# experiment.net
KiCad netlist of a schematic drawn in EAGLE
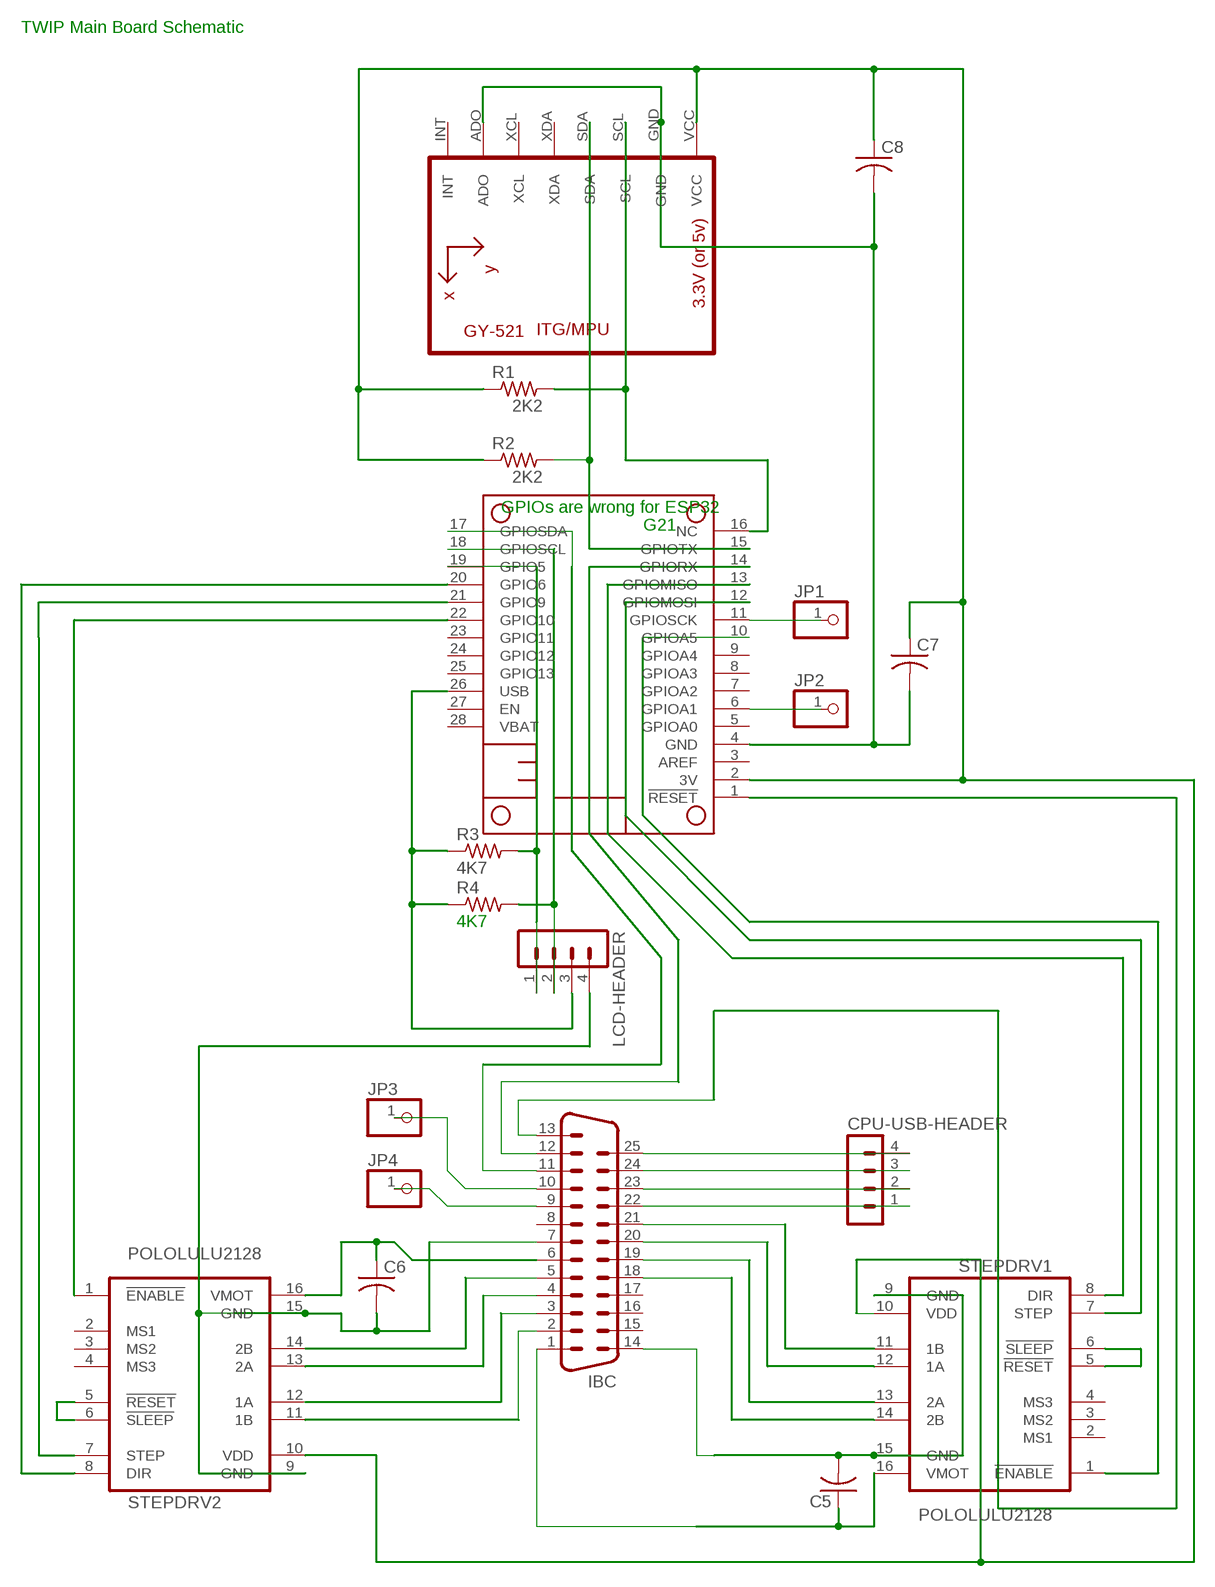
[diagram p0: schematic, sheet 2]

(export (version "E")
  (design (tool "Eeschema 10.0.6"))
  (components
    (comp (ref "C5")
      (value "C-US050-024X044")
      (footprint "eagle-import:C050-024X044")
      (libsource (lib "eagle-import") (part "C-US050-024X044"))
    )
    (comp (ref "C6")
      (value "C-US050-024X044")
      (footprint "eagle-import:C050-024X044")
      (libsource (lib "eagle-import") (part "C-US050-024X044"))
    )
    (comp (ref "C7")
      (value "C-US050-024X044")
      (footprint "eagle-import:C050-024X044")
      (libsource (lib "eagle-import") (part "C-US050-024X044"))
    )
    (comp (ref "C8")
      (value "C-US050-024X044")
      (footprint "eagle-import:C050-024X044")
      (libsource (lib "eagle-import") (part "C-US050-024X044"))
    )
    (comp (ref "CPU-USB-HEADER")
      (value "MA04-1")
      (footprint "eagle-import:MA04-1")
      (libsource (lib "eagle-import") (part "MA04-1"))
    )
    (comp (ref "IBC")
      (value "M25VP")
      (footprint "eagle-import:M25VP")
      (libsource (lib "eagle-import") (part "M25VP"))
    )
    (comp (ref "JP1")
      (value "PINHD-1X1")
      (footprint "eagle-import:1X01")
      (libsource (lib "eagle-import") (part "PINHD-1X1"))
    )
    (comp (ref "JP2")
      (value "PINHD-1X1")
      (footprint "eagle-import:1X01")
      (libsource (lib "eagle-import") (part "PINHD-1X1"))
    )
    (comp (ref "JP3")
      (value "PINHD-1X1")
      (footprint "eagle-import:1X01")
      (libsource (lib "eagle-import") (part "PINHD-1X1"))
    )
    (comp (ref "JP4")
      (value "PINHD-1X1")
      (footprint "eagle-import:1X01")
      (libsource (lib "eagle-import") (part "PINHD-1X1"))
    )
    (comp (ref "LCD-HEADER")
      (value "MA04-1")
      (footprint "eagle-import:MA04-1")
      (libsource (lib "eagle-import") (part "MA04-1"))
    )
    (comp (ref "MS2")
      (value "FEATHERWING_NOHOLES")
      (footprint "eagle-import:FEATHERWING_NOHOLES")
      (libsource (lib "eagle-import") (part "FEATHERWING_NOHOLES"))
    )
    (comp (ref "R1")
      (value "2K2")
      (footprint "eagle-import:0309_12")
      (libsource (lib "eagle-import") (part "R-US_0309/12"))
    )
    (comp (ref "R2")
      (value "2K2")
      (footprint "eagle-import:0309_12")
      (libsource (lib "eagle-import") (part "R-US_0309/12"))
    )
    (comp (ref "R3")
      (value "4K7")
      (footprint "eagle-import:0309_12")
      (libsource (lib "eagle-import") (part "R-US_0309/12"))
    )
    (comp (ref "R4")
      (value "4K7")
      (footprint "eagle-import:0309_12")
      (libsource (lib "eagle-import") (part "R-US_0309/12"))
    )
    (comp (ref "STEPDRV1")
      (value "POLOLULU2128")
      (footprint "eagle-import:POLOLULU2128")
      (libsource (lib "eagle-import") (part "POLOLULU2128"))
    )
    (comp (ref "STEPDRV2")
      (value "POLOLULU2128")
      (footprint "eagle-import:POLOLULU2128")
      (libsource (lib "eagle-import") (part "POLOLULU2128"))
    )
    (comp (ref "U1")
      (value "GY-521MPU6050")
      (footprint "eagle-import:GY-521")
      (libsource (lib "eagle-import") (part "GY-521MPU6050"))
    )
  )
  (nets
    (net (code "1") (name "Net-(C5-Pad2)") (class "Default")
      (node (ref "C5") (pin "2") (pinfunction "2_2") (pintype "passive"))
      (node (ref "IBC") (pin "14") (pinfunction "14_14") (pintype "passive"))
      (node (ref "STEPDRV1") (pin "15") (pinfunction "GND_15") (pintype "power_in"))
      (node (ref "STEPDRV1") (pin "9") (pinfunction "GND_9") (pintype "power_in"))
    )
    (net (code "2") (name "Net-(C6-Pad2)") (class "Default")
      (node (ref "C6") (pin "2") (pinfunction "2_2") (pintype "passive"))
      (node (ref "IBC") (pin "7") (pinfunction "7_7") (pintype "passive"))
      (node (ref "LCD-HEADER") (pin "4") (pinfunction "4_4") (pintype "passive"))
      (node (ref "STEPDRV2") (pin "15") (pinfunction "GND_15") (pintype "power_in"))
      (node (ref "STEPDRV2") (pin "9") (pinfunction "GND_9") (pintype "power_in"))
    )
    (net (code "3") (name "Net-(CPU-USB-HEADER-Pad1)") (class "Default")
      (node (ref "CPU-USB-HEADER") (pin "1") (pinfunction "1_1") (pintype "passive"))
      (node (ref "IBC") (pin "22") (pinfunction "22_22") (pintype "passive"))
    )
    (net (code "4") (name "Net-(CPU-USB-HEADER-Pad2)") (class "Default")
      (node (ref "CPU-USB-HEADER") (pin "2") (pinfunction "2_2") (pintype "passive"))
      (node (ref "IBC") (pin "23") (pinfunction "23_23") (pintype "passive"))
    )
    (net (code "5") (name "Net-(CPU-USB-HEADER-Pad3)") (class "Default")
      (node (ref "CPU-USB-HEADER") (pin "3") (pinfunction "3_3") (pintype "passive"))
      (node (ref "IBC") (pin "24") (pinfunction "24_24") (pintype "passive"))
    )
    (net (code "6") (name "Net-(CPU-USB-HEADER-Pad4)") (class "Default")
      (node (ref "CPU-USB-HEADER") (pin "4") (pinfunction "4_4") (pintype "passive"))
      (node (ref "IBC") (pin "25") (pinfunction "25_25") (pintype "passive"))
    )
    (net (code "7") (name "Net-(IBC-Pad9)") (class "Default")
      (node (ref "IBC") (pin "9") (pinfunction "9_9") (pintype "passive"))
      (node (ref "JP4") (pin "1") (pinfunction "1_1") (pintype "passive"))
    )
    (net (code "8") (name "Net-(IBC-Pad10)") (class "Default")
      (node (ref "IBC") (pin "10") (pinfunction "10_10") (pintype "passive"))
      (node (ref "JP3") (pin "1") (pinfunction "1_1") (pintype "passive"))
    )
    (net (code "9") (name "Net-(MS2-3V)") (class "Default")
      (node (ref "C7") (pin "1") (pinfunction "1_1") (pintype "passive"))
      (node (ref "C8") (pin "1") (pinfunction "1_1") (pintype "passive"))
      (node (ref "MS2") (pin "2") (pinfunction "3V_2") (pintype "power_in"))
      (node (ref "R1") (pin "1") (pinfunction "1_1") (pintype "passive"))
      (node (ref "R2") (pin "1") (pinfunction "1_1") (pintype "passive"))
      (node (ref "STEPDRV1") (pin "10") (pinfunction "VDD_10") (pintype "power_in"))
      (node (ref "STEPDRV2") (pin "10") (pinfunction "VDD_10") (pintype "power_in"))
      (node (ref "U1") (pin "VCC") (pinfunction "VCC_VCC") (pintype "bidirectional"))
    )
    (net (code "10") (name "Net-(MS2-GND)") (class "Default")
      (node (ref "C7") (pin "2") (pinfunction "2_2") (pintype "passive"))
      (node (ref "C8") (pin "2") (pinfunction "2_2") (pintype "passive"))
      (node (ref "MS2") (pin "4") (pinfunction "GND_4") (pintype "power_in"))
      (node (ref "U1") (pin "ADO") (pinfunction "ADO_ADO") (pintype "bidirectional"))
      (node (ref "U1") (pin "GND") (pinfunction "GND_GND") (pintype "bidirectional"))
    )
    (net (code "11") (name "Net-(MS2-GPIO5)") (class "Default")
      (node (ref "LCD-HEADER") (pin "1") (pinfunction "1_1") (pintype "passive"))
      (node (ref "MS2") (pin "19") (pinfunction "GPIO5_19") (pintype "bidirectional"))
      (node (ref "R3") (pin "2") (pinfunction "2_2") (pintype "passive"))
    )
    (net (code "12") (name "Net-(MS2-GPIO6)") (class "Default")
      (node (ref "MS2") (pin "20") (pinfunction "GPIO6_20") (pintype "bidirectional"))
      (node (ref "STEPDRV2") (pin "8") (pinfunction "DIR_8") (pintype "input"))
    )
    (net (code "13") (name "Net-(MS2-GPIO9)") (class "Default")
      (node (ref "MS2") (pin "21") (pinfunction "GPIO9_21") (pintype "bidirectional"))
      (node (ref "STEPDRV2") (pin "7") (pinfunction "STEP_7") (pintype "input"))
    )
    (net (code "14") (name "Net-(MS2-GPIO10)") (class "Default")
      (node (ref "MS2") (pin "22") (pinfunction "GPIO10_22") (pintype "bidirectional"))
      (node (ref "STEPDRV2") (pin "1") (pinfunction "~{ENABLE}_1") (pintype "input"))
    )
    (net (code "15") (name "Net-(MS2-GPIOA1)") (class "Default")
      (node (ref "JP2") (pin "1") (pinfunction "1_1") (pintype "passive"))
      (node (ref "MS2") (pin "6") (pinfunction "GPIOA1_6") (pintype "bidirectional"))
    )
    (net (code "16") (name "Net-(MS2-GPIOA5)") (class "Default")
      (node (ref "MS2") (pin "10") (pinfunction "GPIOA5_10") (pintype "bidirectional"))
      (node (ref "STEPDRV1") (pin "1") (pinfunction "~{ENABLE}_1") (pintype "input"))
    )
    (net (code "17") (name "Net-(MS2-GPIOMISO)") (class "Default")
      (node (ref "MS2") (pin "13") (pinfunction "GPIOMISO_13") (pintype "bidirectional"))
      (node (ref "STEPDRV1") (pin "8") (pinfunction "DIR_8") (pintype "input"))
    )
    (net (code "18") (name "Net-(MS2-GPIOMOSI)") (class "Default")
      (node (ref "MS2") (pin "12") (pinfunction "GPIOMOSI_12") (pintype "bidirectional"))
      (node (ref "STEPDRV1") (pin "7") (pinfunction "STEP_7") (pintype "input"))
    )
    (net (code "19") (name "Net-(MS2-GPIORX)") (class "Default")
      (node (ref "IBC") (pin "12") (pinfunction "12_12") (pintype "passive"))
      (node (ref "MS2") (pin "14") (pinfunction "GPIORX_14") (pintype "bidirectional"))
    )
    (net (code "20") (name "Net-(MS2-GPIOSCK)") (class "Default")
      (node (ref "JP1") (pin "1") (pinfunction "1_1") (pintype "passive"))
      (node (ref "MS2") (pin "11") (pinfunction "GPIOSCK_11") (pintype "bidirectional"))
    )
    (net (code "21") (name "Net-(MS2-GPIOSCL)") (class "Default")
      (node (ref "LCD-HEADER") (pin "2") (pinfunction "2_2") (pintype "passive"))
      (node (ref "MS2") (pin "18") (pinfunction "GPIOSCL_18") (pintype "bidirectional"))
      (node (ref "R4") (pin "2") (pinfunction "2_2") (pintype "passive"))
    )
    (net (code "22") (name "Net-(MS2-GPIOSDA)") (class "Default")
      (node (ref "IBC") (pin "11") (pinfunction "11_11") (pintype "passive"))
      (node (ref "MS2") (pin "17") (pinfunction "GPIOSDA_17") (pintype "bidirectional"))
    )
    (net (code "23") (name "Net-(MS2-GPIOTX)") (class "Default")
      (node (ref "MS2") (pin "15") (pinfunction "GPIOTX_15") (pintype "bidirectional"))
      (node (ref "R2") (pin "2") (pinfunction "2_2") (pintype "passive"))
      (node (ref "U1") (pin "SDA") (pinfunction "SDA_SDA") (pintype "bidirectional"))
    )
    (net (code "24") (name "Net-(MS2-NC)") (class "Default")
      (node (ref "MS2") (pin "16") (pinfunction "NC_16") (pintype "passive"))
      (node (ref "R1") (pin "2") (pinfunction "2_2") (pintype "passive"))
      (node (ref "U1") (pin "SCL") (pinfunction "SCL_SCL") (pintype "bidirectional"))
    )
    (net (code "25") (name "Net-(MS2-USB)") (class "Default")
      (node (ref "LCD-HEADER") (pin "3") (pinfunction "3_3") (pintype "passive"))
      (node (ref "MS2") (pin "26") (pinfunction "USB_26") (pintype "power_in"))
      (node (ref "R3") (pin "1") (pinfunction "1_1") (pintype "passive"))
      (node (ref "R4") (pin "1") (pinfunction "1_1") (pintype "passive"))
    )
    (net (code "26") (name "Net-(MS2-~{RESET})") (class "Default")
      (node (ref "IBC") (pin "13") (pinfunction "13_13") (pintype "passive"))
      (node (ref "MS2") (pin "1") (pinfunction "~{RESET}_1") (pintype "input"))
    )
    (net (code "27") (name "Net-(STEPDRV1-1A)") (class "Default")
      (node (ref "IBC") (pin "20") (pinfunction "20_20") (pintype "passive"))
      (node (ref "STEPDRV1") (pin "12") (pinfunction "1A_12") (pintype "output"))
    )
    (net (code "28") (name "Net-(STEPDRV1-1B)") (class "Default")
      (node (ref "IBC") (pin "21") (pinfunction "21_21") (pintype "passive"))
      (node (ref "STEPDRV1") (pin "11") (pinfunction "1B_11") (pintype "output"))
    )
    (net (code "29") (name "Net-(STEPDRV1-2A)") (class "Default")
      (node (ref "IBC") (pin "19") (pinfunction "19_19") (pintype "passive"))
      (node (ref "STEPDRV1") (pin "13") (pinfunction "2A_13") (pintype "output"))
    )
    (net (code "30") (name "Net-(STEPDRV1-2B)") (class "Default")
      (node (ref "IBC") (pin "18") (pinfunction "18_18") (pintype "passive"))
      (node (ref "STEPDRV1") (pin "14") (pinfunction "2B_14") (pintype "output"))
    )
    (net (code "31") (name "Net-(STEPDRV1-VMOT)") (class "Default")
      (node (ref "C5") (pin "1") (pinfunction "1_1") (pintype "passive"))
      (node (ref "IBC") (pin "1") (pinfunction "1_1") (pintype "passive"))
      (node (ref "STEPDRV1") (pin "16") (pinfunction "VMOT_16") (pintype "power_in"))
    )
    (net (code "32") (name "Net-(STEPDRV1-~{RESET})") (class "Default")
      (node (ref "STEPDRV1") (pin "5") (pinfunction "~{RESET}_5") (pintype "input"))
      (node (ref "STEPDRV1") (pin "6") (pinfunction "~{SLEEP}_6") (pintype "input"))
    )
    (net (code "33") (name "Net-(STEPDRV2-1A)") (class "Default")
      (node (ref "IBC") (pin "3") (pinfunction "3_3") (pintype "passive"))
      (node (ref "STEPDRV2") (pin "12") (pinfunction "1A_12") (pintype "output"))
    )
    (net (code "34") (name "Net-(STEPDRV2-1B)") (class "Default")
      (node (ref "IBC") (pin "2") (pinfunction "2_2") (pintype "passive"))
      (node (ref "STEPDRV2") (pin "11") (pinfunction "1B_11") (pintype "output"))
    )
    (net (code "35") (name "Net-(STEPDRV2-2A)") (class "Default")
      (node (ref "IBC") (pin "4") (pinfunction "4_4") (pintype "passive"))
      (node (ref "STEPDRV2") (pin "13") (pinfunction "2A_13") (pintype "output"))
    )
    (net (code "36") (name "Net-(STEPDRV2-2B)") (class "Default")
      (node (ref "IBC") (pin "5") (pinfunction "5_5") (pintype "passive"))
      (node (ref "STEPDRV2") (pin "14") (pinfunction "2B_14") (pintype "output"))
    )
    (net (code "37") (name "Net-(STEPDRV2-VMOT)") (class "Default")
      (node (ref "C6") (pin "1") (pinfunction "1_1") (pintype "passive"))
      (node (ref "IBC") (pin "6") (pinfunction "6_6") (pintype "passive"))
      (node (ref "STEPDRV2") (pin "16") (pinfunction "VMOT_16") (pintype "power_in"))
    )
    (net (code "38") (name "Net-(STEPDRV2-~{RESET})") (class "Default")
      (node (ref "STEPDRV2") (pin "5") (pinfunction "~{RESET}_5") (pintype "input"))
      (node (ref "STEPDRV2") (pin "6") (pinfunction "~{SLEEP}_6") (pintype "input"))
    )
    (net (code "39") (name "VBAT") (class "Default")
      (node (ref "MS2") (pin "28") (pinfunction "VBAT_28") (pintype "power_in"))
    )
    (net (code "40") (name "unconnected-(IBC-Pad8)") (class "Default")
      (node (ref "IBC") (pin "8") (pinfunction "8_8") (pintype "passive"))
    )
    (net (code "41") (name "unconnected-(IBC-Pad15)") (class "Default")
      (node (ref "IBC") (pin "15") (pinfunction "15_15") (pintype "passive"))
    )
    (net (code "42") (name "unconnected-(IBC-Pad16)") (class "Default")
      (node (ref "IBC") (pin "16") (pinfunction "16_16") (pintype "passive"))
    )
    (net (code "43") (name "unconnected-(IBC-Pad17)") (class "Default")
      (node (ref "IBC") (pin "17") (pinfunction "17_17") (pintype "passive"))
    )
    (net (code "44") (name "unconnected-(MS2-AREF-Pad3)") (class "Default")
      (node (ref "MS2") (pin "3") (pinfunction "AREF_3") (pintype "passive"))
    )
    (net (code "45") (name "unconnected-(MS2-EN-Pad27)") (class "Default")
      (node (ref "MS2") (pin "27") (pinfunction "EN_27") (pintype "passive"))
    )
    (net (code "46") (name "unconnected-(MS2-GPIO11-Pad23)") (class "Default")
      (node (ref "MS2") (pin "23") (pinfunction "GPIO11_23") (pintype "bidirectional"))
    )
    (net (code "47") (name "unconnected-(MS2-GPIO12-Pad24)") (class "Default")
      (node (ref "MS2") (pin "24") (pinfunction "GPIO12_24") (pintype "bidirectional"))
    )
    (net (code "48") (name "unconnected-(MS2-GPIO13-Pad25)") (class "Default")
      (node (ref "MS2") (pin "25") (pinfunction "GPIO13_25") (pintype "bidirectional"))
    )
    (net (code "49") (name "unconnected-(MS2-GPIOA0-Pad5)") (class "Default")
      (node (ref "MS2") (pin "5") (pinfunction "GPIOA0_5") (pintype "bidirectional"))
    )
    (net (code "50") (name "unconnected-(MS2-GPIOA2-Pad7)") (class "Default")
      (node (ref "MS2") (pin "7") (pinfunction "GPIOA2_7") (pintype "bidirectional"))
    )
    (net (code "51") (name "unconnected-(MS2-GPIOA3-Pad8)") (class "Default")
      (node (ref "MS2") (pin "8") (pinfunction "GPIOA3_8") (pintype "bidirectional"))
    )
    (net (code "52") (name "unconnected-(MS2-GPIOA4-Pad9)") (class "Default")
      (node (ref "MS2") (pin "9") (pinfunction "GPIOA4_9") (pintype "bidirectional"))
    )
    (net (code "53") (name "unconnected-(STEPDRV1-MS1-Pad2)") (class "Default")
      (node (ref "STEPDRV1") (pin "2") (pinfunction "MS1_2") (pintype "input"))
    )
    (net (code "54") (name "unconnected-(STEPDRV1-MS2-Pad3)") (class "Default")
      (node (ref "STEPDRV1") (pin "3") (pinfunction "MS2_3") (pintype "input"))
    )
    (net (code "55") (name "unconnected-(STEPDRV1-MS3-Pad4)") (class "Default")
      (node (ref "STEPDRV1") (pin "4") (pinfunction "MS3_4") (pintype "input"))
    )
    (net (code "56") (name "unconnected-(STEPDRV2-MS1-Pad2)") (class "Default")
      (node (ref "STEPDRV2") (pin "2") (pinfunction "MS1_2") (pintype "input"))
    )
    (net (code "57") (name "unconnected-(STEPDRV2-MS2-Pad3)") (class "Default")
      (node (ref "STEPDRV2") (pin "3") (pinfunction "MS2_3") (pintype "input"))
    )
    (net (code "58") (name "unconnected-(STEPDRV2-MS3-Pad4)") (class "Default")
      (node (ref "STEPDRV2") (pin "4") (pinfunction "MS3_4") (pintype "input"))
    )
    (net (code "59") (name "unconnected-(U1-PadINT)") (class "Default")
      (node (ref "U1") (pin "INT") (pinfunction "INT_INT") (pintype "bidirectional"))
    )
    (net (code "60") (name "unconnected-(U1-PadXCL)") (class "Default")
      (node (ref "U1") (pin "XCL") (pinfunction "XCL_XCL") (pintype "bidirectional"))
    )
    (net (code "61") (name "unconnected-(U1-PadXDA)") (class "Default")
      (node (ref "U1") (pin "XDA") (pinfunction "XDA_XDA") (pintype "bidirectional"))
    )
  )
)
